# AiJig.net
KiCad netlist of a schematic drawn in Altium Designer
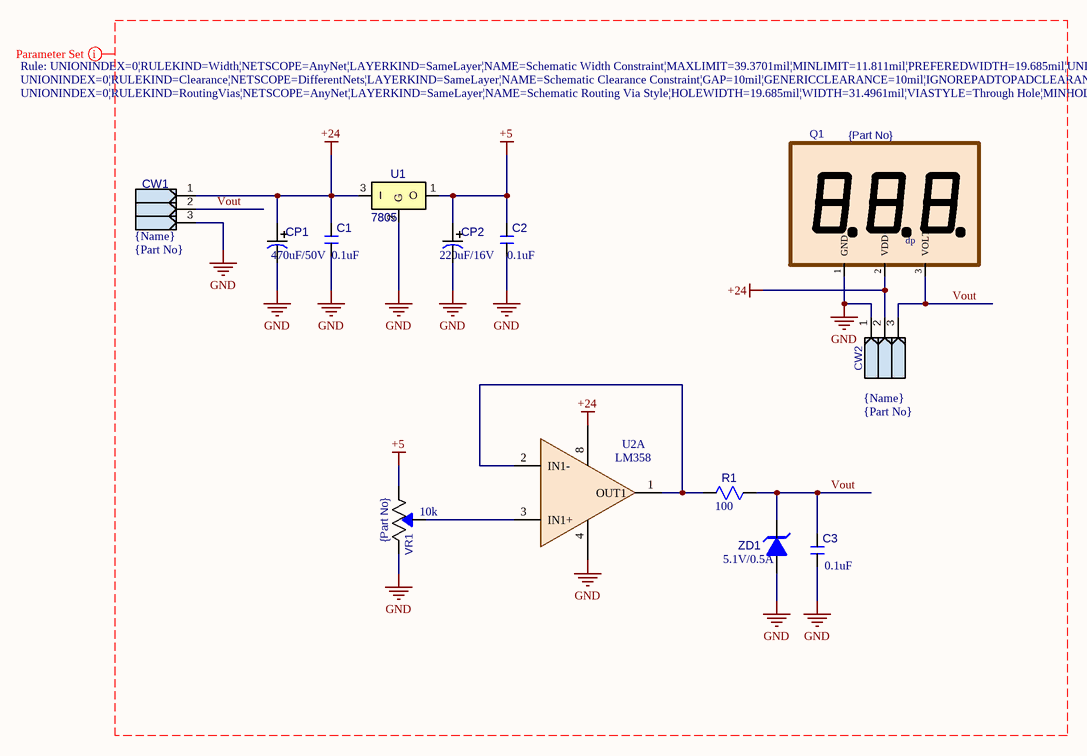
[diagram p0: AiJig.SchDoc]

(export (version "E")
  (design (tool "Eeschema 10.0.6"))
  (components
    (comp (ref "C1")
      (value "CS0805")
      (footprint "CC1608")
      (fields (field (name "PART NO.") "{Part No}") (field (name "규격") "0.1uF"))
      (libsource (lib "KipoAlt") (part "CS_SMT"))
    )
    (comp (ref "C2")
      (value "CS0805")
      (footprint "CC1608")
      (fields (field (name "PART NO.") "{Part No}") (field (name "규격") "0.1uF"))
      (libsource (lib "KipoAlt") (part "CS_SMT"))
    )
    (comp (ref "C3")
      (value "CS0805")
      (footprint "CC1608")
      (fields (field (name "PART NO.") "{Part No}") (field (name "규격") "0.1uF"))
      (libsource (lib "KipoAlt") (part "CS_SMT"))
    )
    (comp (ref "CP1")
      (value "CP8_16")
      (footprint "CP10_SMT")
      (fields (field (name "PART NO.") "{Value}") (field (name "규격") "470uF/50V"))
      (libsource (lib "KipoAlt") (part "CP_SMT"))
    )
    (comp (ref "CP2")
      (value "CP8_16")
      (footprint "CP6_SMT")
      (fields (field (name "PART NO.") "{Value}") (field (name "규격") "220uF/16V"))
      (libsource (lib "KipoAlt") (part "CP_SMT"))
    )
    (comp (ref "CW1")
      (value "SMW250-03L")
      (footprint "SMW250-03L")
      (fields (field (name "NAME") "{Name}") (field (name "PART NO.") "{Part No}"))
      (libsource (lib "KipoAlt") (part "SMW250-03L"))
    )
    (comp (ref "CW2")
      (value "SMW250-03D")
      (footprint "SMW250-03D")
      (fields (field (name "NAME") "{Name}") (field (name "PART NO.") "{Part No}"))
      (libsource (lib "KipoAlt") (part "SMW250-03D"))
    )
    (comp (ref "Q1")
      (value "SND-330B")
      (footprint "VoltMeter")
      (fields (field (name "PART NO.") "{Part No}"))
      (libsource (lib "KipoAlt") (part "VoltMeter"))
    )
    (comp (ref "R1")
      (value "100")
      (footprint "RESC1608X55N")
      (fields (field (name "PART NO.") "{Part No}") (field (name "Comment") "CS"))
      (libsource (lib "KipoAlt") (part "R_SMT"))
    )
    (comp (ref "U1")
      (value "7805")
      (footprint "SOT-89")
      (fields (field (name "PART NO.") "LM78L05 KX") (field (name "Comment") "78XX_SOT89"))
      (libsource (lib "KipoAlt") (part "78XX_SOT89"))
    )
    (comp (ref "U2")
      (value "NCV2904DR")
      (footprint "SOIC127P600X175-8N")
      (description "Dual general-purpose operational amplifier")
      (fields
        (field (name "MOUSER PART NUMBER") "595-LM2904DR")
        (field (name "ARROW PART NUMBER") "LM2904DR")
        (field (name "PART NO.") "LM358")
      )
      (libsource (lib "KipoAlt") (part "NCD2904"))
    )
    (comp (ref "VR1")
      (value "10k")
      (footprint "VR3296")
      (fields (field (name "PART NO.") "{Part No}") (field (name "Comment") "VR"))
      (libsource (lib "KipoAlt") (part "VR"))
    )
    (comp (ref "ZD1")
      (value "5.1V/0.5A")
      (footprint "ZD3216M")
      (description "24V/0.5A")
      (fields (field (name "PART NO.") "BZT52C24 / TCMMSZ5252BW") (field (name "Comment") "ZD_3216"))
      (libsource (lib "KipoAlt") (part "ZD_3216"))
    )
  )
  (nets
    (net (code "1") (name "+5") (class "Default")
      (node (ref "C2") (pin "2") (pintype "passive"))
      (node (ref "CP2") (pin "1") (pinfunction "1_1") (pintype "passive"))
      (node (ref "U1") (pin "1") (pinfunction "O_1") (pintype "passive"))
      (node (ref "VR1") (pin "1") (pintype "passive"))
    )
    (net (code "2") (name "+24") (class "Default")
      (node (ref "C1") (pin "2") (pintype "passive"))
      (node (ref "CP1") (pin "1") (pinfunction "1_1") (pintype "passive"))
      (node (ref "CW1") (pin "1") (pintype "passive"))
      (node (ref "CW2") (pin "2") (pintype "passive"))
      (node (ref "Q1") (pin "2") (pinfunction "VDD_2") (pintype "passive"))
      (node (ref "U1") (pin "3") (pinfunction "I_3") (pintype "passive"))
      (node (ref "U2") (pin "8") (pinfunction "Vdd_8") (pintype "power_in"))
    )
    (net (code "3") (name "/Vout") (class "Default")
      (node (ref "C3") (pin "2") (pintype "passive"))
      (node (ref "CW1") (pin "2") (pintype "passive"))
      (node (ref "CW2") (pin "3") (pintype "passive"))
      (node (ref "Q1") (pin "3") (pinfunction "VOLT_3") (pintype "passive"))
      (node (ref "R1") (pin "1") (pintype "passive"))
      (node (ref "ZD1") (pin "2") (pintype "passive"))
    )
    (net (code "4") (name "GND") (class "Default")
      (node (ref "C1") (pin "1") (pintype "passive"))
      (node (ref "C2") (pin "1") (pintype "passive"))
      (node (ref "C3") (pin "1") (pintype "passive"))
      (node (ref "CP1") (pin "2") (pinfunction "2_2") (pintype "passive"))
      (node (ref "CP2") (pin "2") (pinfunction "2_2") (pintype "passive"))
      (node (ref "CW1") (pin "3") (pintype "passive"))
      (node (ref "CW2") (pin "1") (pintype "passive"))
      (node (ref "Q1") (pin "1") (pinfunction "GND_1") (pintype "passive"))
      (node (ref "U1") (pin "2") (pinfunction "G_2") (pintype "passive"))
      (node (ref "U2") (pin "4") (pinfunction "GND_4") (pintype "power_in"))
      (node (ref "VR1") (pin "3") (pintype "passive"))
      (node (ref "ZD1") (pin "1") (pintype "passive"))
    )
    (net (code "5") (name "Net-(U2A-IN1+)") (class "Default")
      (node (ref "U2") (pin "3") (pinfunction "IN1+_3") (pintype "passive"))
      (node (ref "VR1") (pin "2") (pintype "passive"))
    )
    (net (code "6") (name "Net-(U2A-IN1-)") (class "Default")
      (node (ref "R1") (pin "2") (pintype "passive"))
      (node (ref "U2") (pin "1") (pinfunction "OUT1_1") (pintype "passive"))
      (node (ref "U2") (pin "2") (pinfunction "IN1-_2") (pintype "passive"))
    )
    (net (code "7") (name "unconnected-(Q1-Pad6)") (class "Default")
      (node (ref "Q1") (pin "6") (pintype "passive"))
    )
    (net (code "8") (name "unconnected-(U1-Pad4)") (class "Default")
      (node (ref "U1") (pin "4") (pintype "passive"))
    )
  )
)
